# PCA10_NBU1012_Cable.net
KiCad netlist of a schematic drawn in Altium Designer
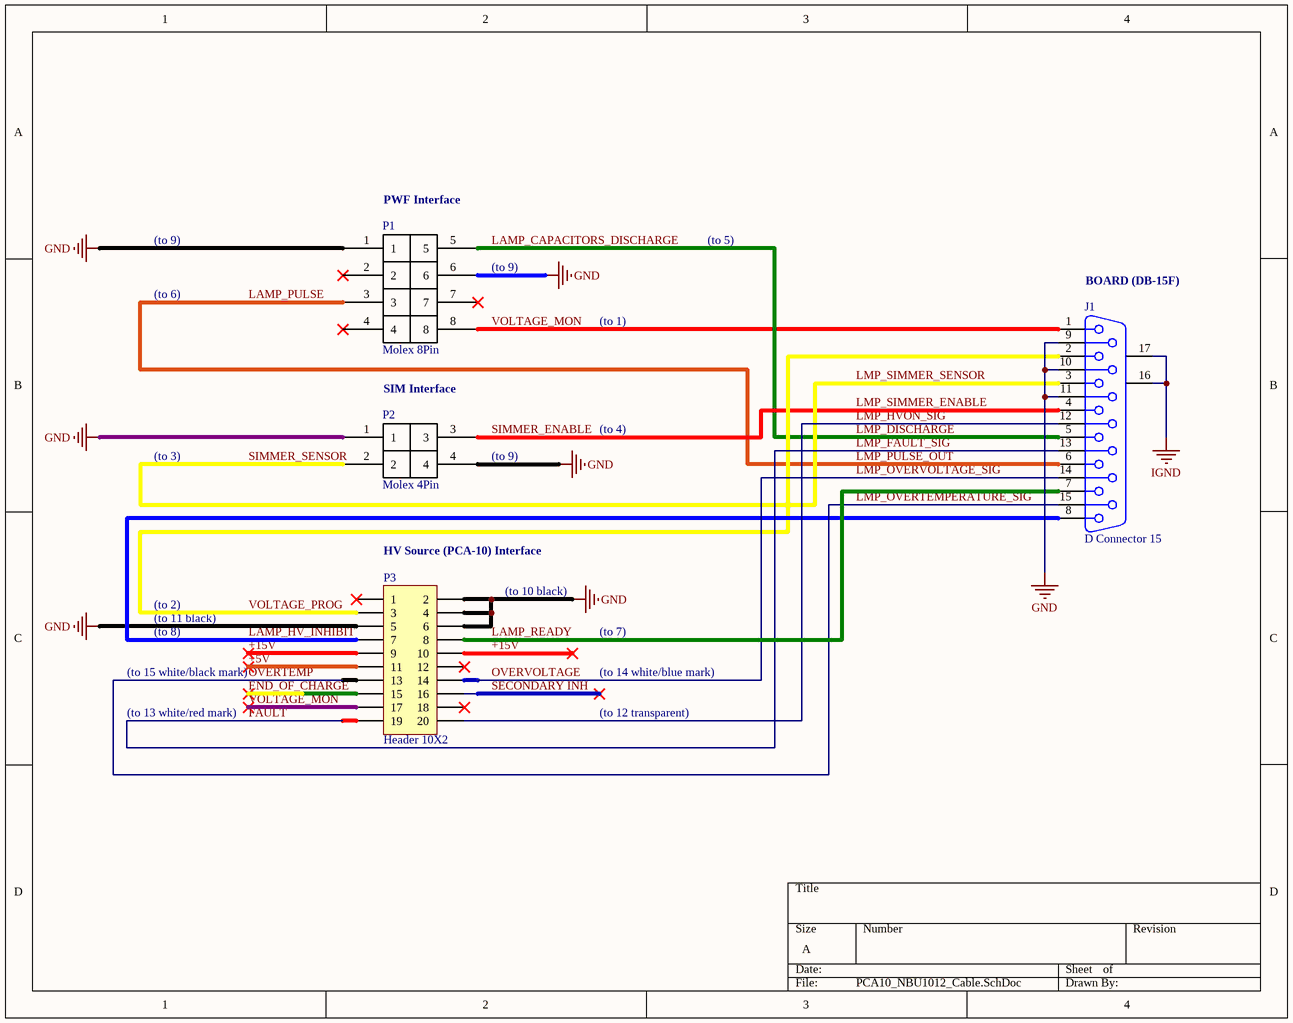
[diagram p0: PCA10_NBU1012_Cable.SchDoc]

(export (version "E")
  (design (tool "Eeschema 10.0.6"))
  (components
    (comp (ref "J1")
      (value "D Connector 15")
      (footprint "DSUB1.385-2H15")
      (description "Receptacle Assembly, 15 Position, Right Angle")
      (fields (field (name "PUBLISHER") "Altium Limited"))
      (libsource (lib "Connectors") (part "D Connector 15"))
    )
    (comp (ref "P1") (value "Molex 8Pin") (libsource (lib "Molex_Connectors") (part "Molex 8Pin")))
    (comp (ref "P2") (value "Molex 4Pin") (libsource (lib "Molex_Connectors") (part "Molex 4Pin")))
    (comp (ref "P3")
      (value "Header 10X2")
      (footprint "HDR2X10")
      (description "Header, 10-Pin, Dual row")
      (fields (field (name "PUBLISHER") "Altium Limited"))
      (libsource (lib "Miscellaneous Connectors") (part "Header 10X2"))
    )
  )
  (nets
    (net (code "1") (name "/+5V") (class "Default")
      (node (ref "P3") (pin "11") (pinfunction "11_11") (pintype "passive+no_connect"))
    )
    (net (code "2") (name "/+15V") (class "Default")
      (node (ref "P3") (pin "10") (pinfunction "10_10") (pintype "passive"))
      (node (ref "P3") (pin "9") (pinfunction "9_9") (pintype "passive"))
    )
    (net (code "3") (name "/END_OF_CHARGE") (class "Default")
      (node (ref "P3") (pin "15") (pinfunction "15_15") (pintype "passive+no_connect"))
    )
    (net (code "4") (name "/FAULT") (class "Default")
      (node (ref "J1") (pin "13") (pinfunction "13_13") (pintype "passive"))
      (node (ref "P3") (pin "19") (pinfunction "19_19") (pintype "passive"))
    )
    (net (code "5") (name "/LAMP_CAPACITORS_DISCHARGE") (class "Default")
      (node (ref "J1") (pin "5") (pinfunction "5_5") (pintype "passive"))
      (node (ref "P1") (pin "5") (pinfunction "5_5") (pintype "passive"))
    )
    (net (code "6") (name "/LAMP_HV_INHIBIT") (class "Default")
      (node (ref "J1") (pin "8") (pinfunction "8_8") (pintype "passive"))
      (node (ref "P3") (pin "7") (pinfunction "7_7") (pintype "passive"))
    )
    (net (code "7") (name "/LAMP_PULSE") (class "Default")
      (node (ref "J1") (pin "6") (pinfunction "6_6") (pintype "passive"))
      (node (ref "P1") (pin "3") (pinfunction "3_3") (pintype "passive"))
    )
    (net (code "8") (name "/LAMP_READY") (class "Default")
      (node (ref "J1") (pin "7") (pinfunction "7_7") (pintype "passive"))
      (node (ref "P3") (pin "8") (pinfunction "8_8") (pintype "passive"))
    )
    (net (code "9") (name "/LMP_HVON_SIG") (class "Default")
      (node (ref "J1") (pin "12") (pinfunction "12_12") (pintype "passive"))
      (node (ref "P3") (pin "20") (pinfunction "20_20") (pintype "passive"))
    )
    (net (code "10") (name "/LMP_OVERTEMPERATURE_SIG") (class "Default")
      (node (ref "J1") (pin "15") (pinfunction "15_15") (pintype "passive"))
      (node (ref "P3") (pin "13") (pinfunction "13_13") (pintype "passive"))
    )
    (net (code "11") (name "/LMP_OVERVOLTAGE_SIG") (class "Default")
      (node (ref "J1") (pin "14") (pinfunction "14_14") (pintype "passive"))
      (node (ref "P3") (pin "14") (pinfunction "14_14") (pintype "passive"))
    )
    (net (code "12") (name "/LMP_SIMMER_ENABLE") (class "Default")
      (node (ref "J1") (pin "4") (pinfunction "4_4") (pintype "passive"))
      (node (ref "P2") (pin "3") (pinfunction "3_3") (pintype "passive"))
    )
    (net (code "13") (name "/LMP_SIMMER_SENSOR") (class "Default")
      (node (ref "J1") (pin "3") (pinfunction "3_3") (pintype "passive"))
      (node (ref "P2") (pin "2") (pinfunction "2_2") (pintype "passive"))
    )
    (net (code "14") (name "/SECONDARY INH") (class "Default")
      (node (ref "P3") (pin "16") (pinfunction "16_16") (pintype "passive+no_connect"))
    )
    (net (code "15") (name "/VOLTAGE_MON") (class "Default")
      (node (ref "J1") (pin "1") (pinfunction "1_1") (pintype "passive"))
      (node (ref "P1") (pin "8") (pinfunction "8_8") (pintype "passive"))
      (node (ref "P3") (pin "17") (pinfunction "17_17") (pintype "passive"))
    )
    (net (code "16") (name "/VOLTAGE_PROG") (class "Default")
      (node (ref "J1") (pin "2") (pinfunction "2_2") (pintype "passive"))
      (node (ref "P3") (pin "3") (pinfunction "3_3") (pintype "passive"))
    )
    (net (code "17") (name "GND") (class "Default")
      (node (ref "J1") (pin "10") (pinfunction "10_10") (pintype "passive"))
      (node (ref "J1") (pin "11") (pinfunction "11_11") (pintype "passive"))
      (node (ref "J1") (pin "9") (pinfunction "9_9") (pintype "passive"))
      (node (ref "P1") (pin "1") (pinfunction "1_1") (pintype "passive"))
      (node (ref "P1") (pin "6") (pinfunction "6_6") (pintype "passive"))
      (node (ref "P2") (pin "1") (pinfunction "1_1") (pintype "passive"))
      (node (ref "P2") (pin "4") (pinfunction "4_4") (pintype "passive"))
      (node (ref "P3") (pin "2") (pinfunction "2_2") (pintype "passive"))
      (node (ref "P3") (pin "4") (pinfunction "4_4") (pintype "passive"))
      (node (ref "P3") (pin "5") (pinfunction "5_5") (pintype "passive"))
      (node (ref "P3") (pin "6") (pinfunction "6_6") (pintype "passive"))
    )
    (net (code "18") (name "IGND") (class "Default")
      (node (ref "J1") (pin "16") (pinfunction "MH1_16") (pintype "passive"))
      (node (ref "J1") (pin "17") (pinfunction "MH2_17") (pintype "passive"))
    )
    (net (code "19") (name "unconnected-(P1-Pad2)") (class "Default")
      (node (ref "P1") (pin "2") (pinfunction "2_2") (pintype "passive+no_connect"))
    )
    (net (code "20") (name "unconnected-(P1-Pad4)") (class "Default")
      (node (ref "P1") (pin "4") (pinfunction "4_4") (pintype "passive+no_connect"))
    )
    (net (code "21") (name "unconnected-(P1-Pad7)") (class "Default")
      (node (ref "P1") (pin "7") (pinfunction "7_7") (pintype "passive+no_connect"))
    )
    (net (code "22") (name "unconnected-(P3-Pad1)") (class "Default")
      (node (ref "P3") (pin "1") (pinfunction "1_1") (pintype "passive+no_connect"))
    )
    (net (code "23") (name "unconnected-(P3-Pad12)") (class "Default")
      (node (ref "P3") (pin "12") (pinfunction "12_12") (pintype "passive+no_connect"))
    )
    (net (code "24") (name "unconnected-(P3-Pad18)") (class "Default")
      (node (ref "P3") (pin "18") (pinfunction "18_18") (pintype "passive+no_connect"))
    )
  )
)
